# Buck.net
KiCad netlist of a schematic drawn in Altium Designer
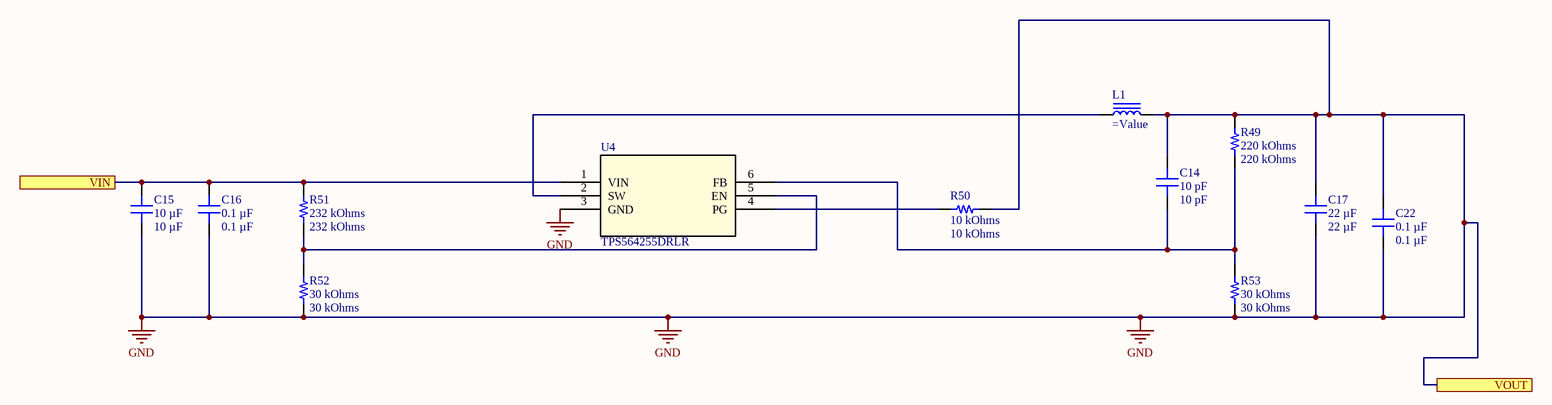
[diagram p0: Buck.SchDoc]

(export (version "E")
  (design (tool "Eeschema 10.0.6"))
  (components
    (comp (ref "C14")
      (value "10 pF")
      (footprint "CAP 0805_2012")
      (description "CAP CER 10PF 250V C0G/NP0 0805")
      (fields (field (name "PART NUMBER") "GQM2195C2E100JB12D") (field (name "ALTIUM_VALUE") "10 pF"))
      (libsource (lib "Celestial Altium Library - altium_library") (part "Capacitor"))
    )
    (comp (ref "C15")
      (value "10 µF")
      (footprint "CAP 0805_2012")
      (description "CAP CER 10UF 10V X7S 0805")
      (fields (field (name "PART NUMBER") "CL21Y106KPQVPNE") (field (name "ALTIUM_VALUE") "10 µF"))
      (libsource (lib "Celestial Altium Library - altium_library") (part "Capacitor"))
    )
    (comp (ref "C16")
      (value "0.1 µF")
      (footprint "CAP 0805_2012")
      (description "CAP CER 0.1UF 50V X7R 0805")
      (fields (field (name "PART NUMBER") "CC0805MRX7R9BB104") (field (name "ALTIUM_VALUE") "0.1 µF"))
      (libsource (lib "Celestial Altium Library - altium_library") (part "Capacitor"))
    )
    (comp (ref "C17")
      (value "22 µF")
      (footprint "CAP 0805_2012")
      (description "CAP CER 22UF 16V X5R 0805")
      (fields (field (name "PART NUMBER") "CL21A226KOQNNNE") (field (name "ALTIUM_VALUE") "22 µF"))
      (libsource (lib "Celestial Altium Library - altium_library") (part "Capacitor"))
    )
    (comp (ref "C22")
      (value "0.1 µF")
      (footprint "CAP 0805_2012")
      (description "CAP CER 0.1UF 50V X7R 0805")
      (fields (field (name "PART NUMBER") "CC0805MRX7R9BB104") (field (name "ALTIUM_VALUE") "0.1 µF"))
      (libsource (lib "Celestial Altium Library - altium_library") (part "Capacitor"))
    )
    (comp (ref "L1")
      (value "~")
      (footprint "WURTH WE-PD 1245")
      (description "FIXED IND 4.7UH 5.2A 16 MOHM SMD")
      (fields (field (name "PART NUMBER") "7447715004"))
      (libsource (lib "Celestial Altium Library - altium_library") (part "Inductor"))
    )
    (comp (ref "R49")
      (value "220 kOhms")
      (footprint "RES 0805_2012")
      (description "RES 220K OHM 1% 1/3W 0805")
      (fields (field (name "PART NUMBER") "CRGP0805F220K") (field (name "ALTIUM_VALUE") "220 kOhms"))
      (libsource (lib "Celestial Altium Library - altium_library") (part "Resistor"))
    )
    (comp (ref "R50")
      (value "10 kOhms")
      (footprint "RES 0805_2012")
      (description "RES 10K OHM 0.1% 1/10W 0805")
      (fields (field (name "PART NUMBER") "RNCS0805BKE10K0") (field (name "ALTIUM_VALUE") "10 kOhms"))
      (libsource (lib "Celestial Altium Library - altium_library") (part "Resistor"))
    )
    (comp (ref "R51")
      (value "232 kOhms")
      (footprint "RES 0805_2012")
      (description "RES SMD 232K OHM 1% 1/8W 0805")
      (fields (field (name "PART NUMBER") "CRCW0805232KFKEA") (field (name "ALTIUM_VALUE") "232 kOhms"))
      (libsource (lib "Celestial Altium Library - altium_library") (part "Resistor"))
    )
    (comp (ref "R52")
      (value "30 kOhms")
      (footprint "RES 0805_2012")
      (description "RES 30K OHM 0.5% 1/8W 0805")
      (fields (field (name "PART NUMBER") "RNCF0805DTE30K0") (field (name "ALTIUM_VALUE") "30 kOhms"))
      (libsource (lib "Celestial Altium Library - altium_library") (part "Resistor"))
    )
    (comp (ref "R53")
      (value "30 kOhms")
      (footprint "RES 0805_2012")
      (description "RES 30K OHM 0.5% 1/8W 0805")
      (fields (field (name "PART NUMBER") "RNCF0805DTE30K0") (field (name "ALTIUM_VALUE") "30 kOhms"))
      (libsource (lib "Celestial Altium Library - altium_library") (part "Resistor"))
    )
    (comp (ref "U4")
      (value "TPS564255DRLR")
      (footprint "TPS564255DRLR:TPS564242DRLR_TEX")
      (description "No Description Available")
      (fields (field (name "COPYRIGHT") "Copyright (C) 2023 Ultra Librarian. All rights reserved."))
      (libsource (lib "TPS564255DRLR") (part "TPS564255DRLR"))
    )
  )
  (nets
    (net (code "1") (name "/VIN") (class "Default")
      (node (ref "C15") (pin "2") (pinfunction "2_2") (pintype "passive"))
      (node (ref "C16") (pin "2") (pinfunction "2_2") (pintype "passive"))
      (node (ref "R51") (pin "2") (pinfunction "2_2") (pintype "passive"))
      (node (ref "U4") (pin "1") (pinfunction "VIN_1") (pintype "power_in"))
    )
    (net (code "2") (name "GND") (class "Default")
      (node (ref "C14") (pin "2") (pinfunction "2_2") (pintype "passive"))
      (node (ref "C15") (pin "1") (pinfunction "1_1") (pintype "passive"))
      (node (ref "C16") (pin "1") (pinfunction "1_1") (pintype "passive"))
      (node (ref "C17") (pin "1") (pinfunction "1_1") (pintype "passive"))
      (node (ref "C17") (pin "2") (pinfunction "2_2") (pintype "passive"))
      (node (ref "C22") (pin "1") (pinfunction "1_1") (pintype "passive"))
      (node (ref "C22") (pin "2") (pinfunction "2_2") (pintype "passive"))
      (node (ref "L1") (pin "2") (pinfunction "2_2") (pintype "passive"))
      (node (ref "R49") (pin "2") (pinfunction "2_2") (pintype "passive"))
      (node (ref "R50") (pin "2") (pinfunction "2_2") (pintype "passive"))
      (node (ref "R52") (pin "1") (pinfunction "1_1") (pintype "passive"))
      (node (ref "R53") (pin "1") (pinfunction "1_1") (pintype "passive"))
      (node (ref "U4") (pin "3") (pinfunction "GND_3") (pintype "power_in"))
    )
    (net (code "3") (name "Net-(U4-EN)") (class "Default")
      (node (ref "R51") (pin "1") (pinfunction "1_1") (pintype "passive"))
      (node (ref "R52") (pin "2") (pinfunction "2_2") (pintype "passive"))
      (node (ref "U4") (pin "5") (pinfunction "EN_5") (pintype "passive"))
    )
    (net (code "4") (name "Net-(U4-FB)") (class "Default")
      (node (ref "C14") (pin "1") (pinfunction "1_1") (pintype "passive"))
      (node (ref "R49") (pin "1") (pinfunction "1_1") (pintype "passive"))
      (node (ref "R53") (pin "2") (pinfunction "2_2") (pintype "passive"))
      (node (ref "U4") (pin "6") (pinfunction "FB_6") (pintype "passive"))
    )
    (net (code "5") (name "Net-(U4-PG)") (class "Default")
      (node (ref "R50") (pin "1") (pinfunction "1_1") (pintype "passive"))
      (node (ref "U4") (pin "4") (pinfunction "PG_4") (pintype "passive"))
    )
    (net (code "6") (name "Net-(U4-SW)") (class "Default")
      (node (ref "L1") (pin "1") (pinfunction "1_1") (pintype "passive"))
      (node (ref "U4") (pin "2") (pinfunction "SW_2") (pintype "power_in"))
    )
  )
)
